# IO_connections.net
KiCad netlist of a schematic drawn in Altium Designer
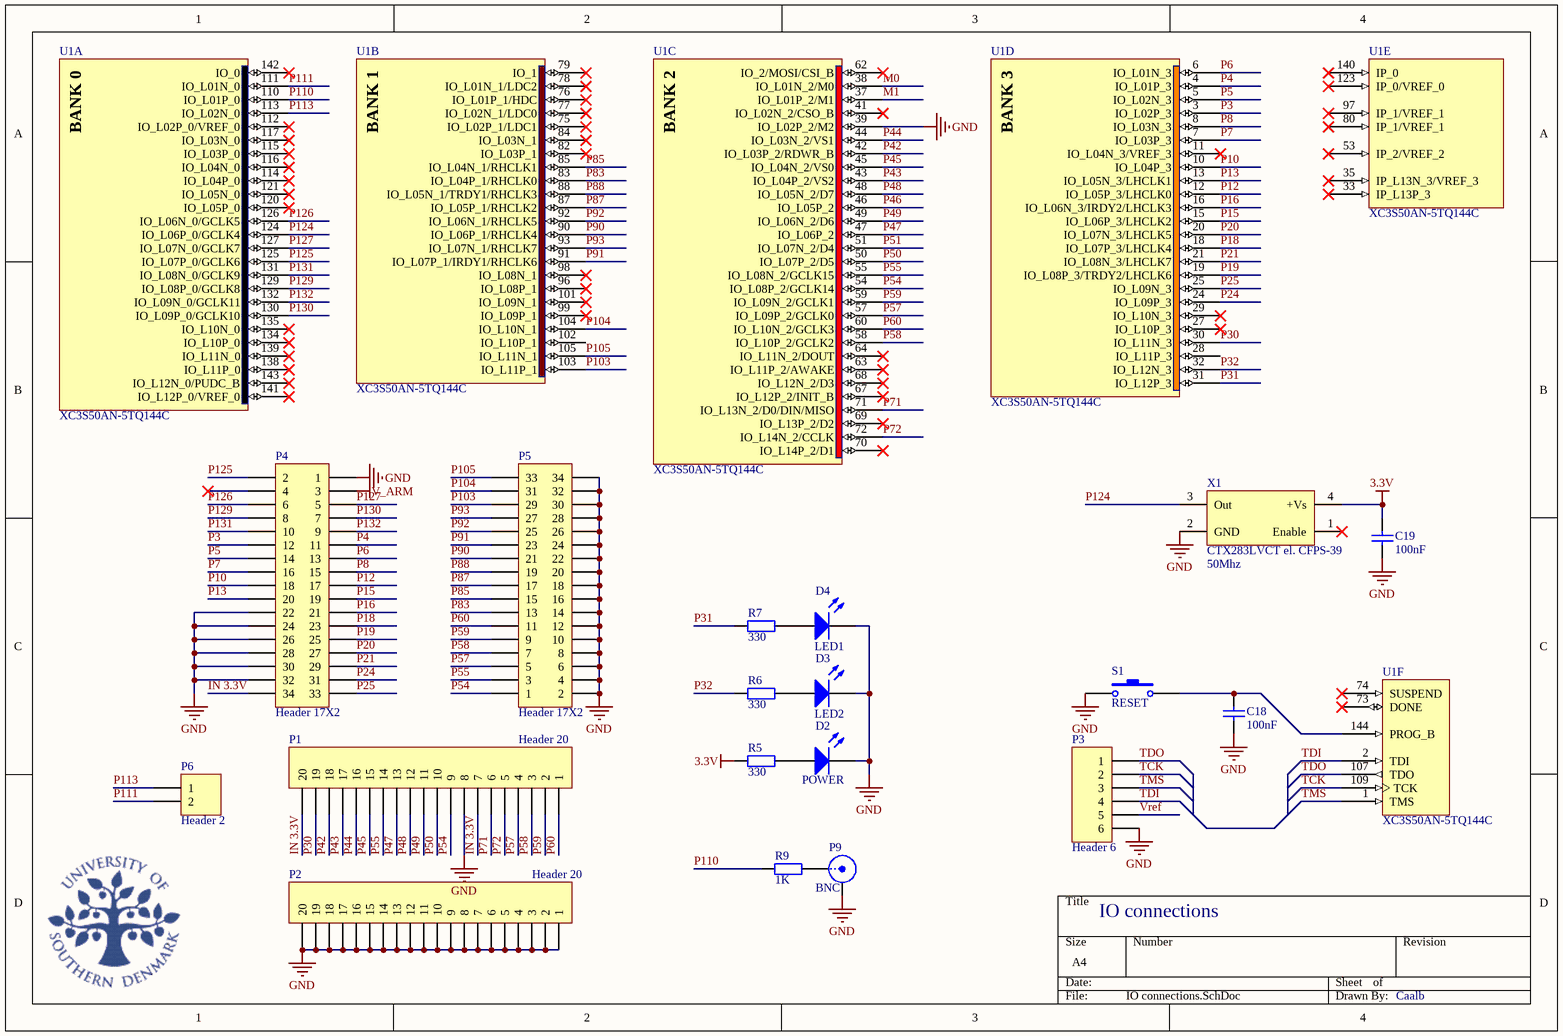
[diagram p0: IO connections.SchDoc]

(export (version "E")
  (design (tool "Eeschema 10.0.6"))
  (components
    (comp (ref "C18")
      (value "100nF")
      (footprint "0805")
      (description "!Capacitor")
      (fields (field (name "Comment") "Cap") (field (name "PUBLISHER") "Altium Limited"))
      (libsource (lib "Miscellaneous Devices") (part "Cap"))
    )
    (comp (ref "C19")
      (value "100nF")
      (footprint "0805")
      (description "!Capacitor")
      (fields (field (name "Comment") "Cap") (field (name "PUBLISHER") "Altium Limited"))
      (libsource (lib "Miscellaneous Devices") (part "Cap"))
    )
    (comp (ref "D2")
      (value "POWER")
      (footprint "LED1206")
      (description "LED")
      (fields (field (name "PUBLISHER") "Altium Limited"))
      (libsource (lib "Miscellaneous Devices") (part "LED0"))
    )
    (comp (ref "D3")
      (value "LED2")
      (footprint "LED1206")
      (description "LED")
      (fields (field (name "PUBLISHER") "Altium Limited"))
      (libsource (lib "Miscellaneous Devices") (part "LED0"))
    )
    (comp (ref "D4")
      (value "LED1")
      (footprint "LED1206")
      (description "LED")
      (fields (field (name "PUBLISHER") "Altium Limited"))
      (libsource (lib "Miscellaneous Devices") (part "LED0"))
    )
    (comp (ref "P1")
      (value "Header 20")
      (footprint "HDR1X20 Kant Special")
      (description "Header, 20-Pin")
      (fields (field (name "PUBLISHER") "Altium Limited"))
      (libsource (lib "Miscellaneous Connectors") (part "Header 20"))
    )
    (comp (ref "P2")
      (value "Header 20")
      (footprint "HDR1X20 Kant")
      (description "Header, 20-Pin")
      (fields (field (name "PUBLISHER") "Altium Limited"))
      (libsource (lib "Miscellaneous Connectors") (part "Header 20"))
    )
    (comp (ref "P3")
      (value "Header 6")
      (footprint "HDR1X6")
      (description "Header, 6-Pin")
      (fields (field (name "PUBLISHER") "Altium Limited"))
      (libsource (lib "Miscellaneous Connectors") (part "Header 6"))
    )
    (comp (ref "P4")
      (value "Header 17X2")
      (footprint "HDR2X10/17FLAD Combi")
      (description "Header, 17-Pin, Dual row")
      (fields (field (name "PUBLISHER") "Altium Limited"))
      (libsource (lib "") (part "Header 17X2_1"))
    )
    (comp (ref "P5")
      (value "Header 17X2")
      (footprint "HDR2X17FLAD Special")
      (description "Header, 17-Pin, Dual row")
      (fields (field (name "PUBLISHER") "Altium Limited"))
      (libsource (lib "Miscellaneous Connectors") (part "Header 17X2"))
    )
    (comp (ref "P6")
      (value "Header 2")
      (footprint "HDR1X2")
      (description "Header, 2-Pin")
      (fields (field (name "PUBLISHER") "Altium Limited"))
      (libsource (lib "Miscellaneous Connectors") (part "Header 2"))
    )
    (comp (ref "P9")
      (value "BNC")
      (footprint "Miniature Coaxial Connectors")
      (description "Miniature Coaxial Connectors")
      (fields (field (name "PUBLISHER") "Altium Limited"))
      (libsource (lib "Miscellaneous Connectors") (part "BNC"))
    )
    (comp (ref "R5")
      (value "330")
      (footprint "0805")
      (description "!Resistor")
      (fields (field (name "Comment") "Res2") (field (name "PUBLISHER") "Altium Limited"))
      (libsource (lib "Miscellaneous Devices") (part "Res2"))
    )
    (comp (ref "R6")
      (value "330")
      (footprint "0805")
      (description "!Resistor")
      (fields (field (name "Comment") "Res2") (field (name "PUBLISHER") "Altium Limited"))
      (libsource (lib "Miscellaneous Devices") (part "Res2"))
    )
    (comp (ref "R7")
      (value "330")
      (footprint "0805")
      (description "!Resistor")
      (fields (field (name "Comment") "Res2") (field (name "PUBLISHER") "Altium Limited"))
      (libsource (lib "Miscellaneous Devices") (part "Res2"))
    )
    (comp (ref "R9")
      (value "1K")
      (footprint "0805")
      (description "!Resistor")
      (fields (field (name "Comment") "Res2") (field (name "PUBLISHER") "Altium Limited"))
      (libsource (lib "") (part "Res2_1"))
    )
    (comp (ref "S1")
      (value "RESET")
      (footprint "B3U-3000P")
      (description "Switch")
      (fields (field (name "PUBLISHER") "Altium Limited"))
      (libsource (lib "Miscellaneous Devices") (part "SW-PB"))
    )
    (comp (ref "U1")
      (value "XC3S50AN-5TQ144C")
      (footprint "TQ144_L")
      (description "Spartan-3AN Non-Volatile FPGA, 108 User I/Os, 144-Pin TQFP, High Performance, Commercial Grade")
      (fields (field (name "PUBLISHER") "Altium Limited"))
      (libsource (lib "Xilinx Spartan-3AN") (part "XC3S50AN-5TQ144C"))
    )
    (comp (ref "X1")
      (value "CTX283LVCT el. CFPS-39")
      (footprint "CB3LV-3C/CFPS-39")
      (description "3.3V, ultra minature surface mount oscillator")
      (fields (field (name "ALTIUM_VALUE") "50Mhz"))
      (libsource (lib "DivLib") (part "CFPS-39"))
    )
  )
  (nets
    (net (code "1") (name "/IN 3.3V") (class "Default")
      (node (ref "P1") (pin "20") (pinfunction "20_20") (pintype "passive"))
      (node (ref "P1") (pin "7") (pinfunction "7_7") (pintype "passive"))
      (node (ref "P4") (pin "34") (pinfunction "34_34") (pintype "passive"))
    )
    (net (code "2") (name "/M0") (class "Default")
      (node (ref "U1") (pin "38") (pinfunction "IO_L01N_2/M0_38") (pintype "bidirectional"))
    )
    (net (code "3") (name "/M1") (class "Default")
      (node (ref "U1") (pin "37") (pinfunction "IO_L01P_2/M1_37") (pintype "bidirectional"))
    )
    (net (code "4") (name "/P3") (class "Default")
      (node (ref "P4") (pin "12") (pinfunction "12_12") (pintype "passive"))
      (node (ref "U1") (pin "3") (pinfunction "IO_L02P_3_3") (pintype "bidirectional"))
    )
    (net (code "5") (name "/P4") (class "Default")
      (node (ref "P4") (pin "11") (pinfunction "11_11") (pintype "passive"))
      (node (ref "U1") (pin "4") (pinfunction "IO_L01P_3_4") (pintype "bidirectional"))
    )
    (net (code "6") (name "/P5") (class "Default")
      (node (ref "P4") (pin "14") (pinfunction "14_14") (pintype "passive"))
      (node (ref "U1") (pin "5") (pinfunction "IO_L02N_3_5") (pintype "bidirectional"))
    )
    (net (code "7") (name "/P6") (class "Default")
      (node (ref "P4") (pin "13") (pinfunction "13_13") (pintype "passive"))
      (node (ref "U1") (pin "6") (pinfunction "IO_L01N_3_6") (pintype "bidirectional"))
    )
    (net (code "8") (name "/P7") (class "Default")
      (node (ref "P4") (pin "16") (pinfunction "16_16") (pintype "passive"))
      (node (ref "U1") (pin "7") (pinfunction "IO_L03P_3_7") (pintype "bidirectional"))
    )
    (net (code "9") (name "/P8") (class "Default")
      (node (ref "P4") (pin "15") (pinfunction "15_15") (pintype "passive"))
      (node (ref "U1") (pin "8") (pinfunction "IO_L03N_3_8") (pintype "bidirectional"))
    )
    (net (code "10") (name "/P10") (class "Default")
      (node (ref "P4") (pin "18") (pinfunction "18_18") (pintype "passive"))
      (node (ref "U1") (pin "10") (pinfunction "IO_L04P_3_10") (pintype "bidirectional"))
    )
    (net (code "11") (name "/P12") (class "Default")
      (node (ref "P4") (pin "17") (pinfunction "17_17") (pintype "passive"))
      (node (ref "U1") (pin "12") (pinfunction "IO_L05P_3/LHCLK0_12") (pintype "bidirectional"))
    )
    (net (code "12") (name "/P13") (class "Default")
      (node (ref "P4") (pin "20") (pinfunction "20_20") (pintype "passive"))
      (node (ref "U1") (pin "13") (pinfunction "IO_L05N_3/LHCLK1_13") (pintype "bidirectional"))
    )
    (net (code "13") (name "/P15") (class "Default")
      (node (ref "P4") (pin "19") (pinfunction "19_19") (pintype "passive"))
      (node (ref "U1") (pin "15") (pinfunction "IO_L06P_3/LHCLK2_15") (pintype "bidirectional"))
    )
    (net (code "14") (name "/P16") (class "Default")
      (node (ref "P4") (pin "21") (pinfunction "21_21") (pintype "passive"))
      (node (ref "U1") (pin "16") (pinfunction "IO_L06N_3/IRDY2/LHCLK3_16") (pintype "bidirectional"))
    )
    (net (code "15") (name "/P18") (class "Default")
      (node (ref "P4") (pin "23") (pinfunction "23_23") (pintype "passive"))
      (node (ref "U1") (pin "18") (pinfunction "IO_L07P_3/LHCLK4_18") (pintype "bidirectional"))
    )
    (net (code "16") (name "/P19") (class "Default")
      (node (ref "P4") (pin "25") (pinfunction "25_25") (pintype "passive"))
      (node (ref "U1") (pin "19") (pinfunction "IO_L08P_3/TRDY2/LHCLK6_19") (pintype "bidirectional"))
    )
    (net (code "17") (name "/P20") (class "Default")
      (node (ref "P4") (pin "27") (pinfunction "27_27") (pintype "passive"))
      (node (ref "U1") (pin "20") (pinfunction "IO_L07N_3/LHCLK5_20") (pintype "bidirectional"))
    )
    (net (code "18") (name "/P21") (class "Default")
      (node (ref "P4") (pin "29") (pinfunction "29_29") (pintype "passive"))
      (node (ref "U1") (pin "21") (pinfunction "IO_L08N_3/LHCLK7_21") (pintype "bidirectional"))
    )
    (net (code "19") (name "/P24") (class "Default")
      (node (ref "P4") (pin "31") (pinfunction "31_31") (pintype "passive"))
      (node (ref "U1") (pin "24") (pinfunction "IO_L09P_3_24") (pintype "bidirectional"))
    )
    (net (code "20") (name "/P25") (class "Default")
      (node (ref "P4") (pin "33") (pinfunction "33_33") (pintype "passive"))
      (node (ref "U1") (pin "25") (pinfunction "IO_L09N_3_25") (pintype "bidirectional"))
    )
    (net (code "21") (name "/P30") (class "Default")
      (node (ref "P1") (pin "19") (pinfunction "19_19") (pintype "passive"))
      (node (ref "U1") (pin "30") (pinfunction "IO_L11N_3_30") (pintype "bidirectional"))
    )
    (net (code "22") (name "/P31") (class "Default")
      (node (ref "R7") (pin "2") (pinfunction "2_2") (pintype "passive"))
      (node (ref "U1") (pin "31") (pinfunction "IO_L12P_3_31") (pintype "bidirectional"))
    )
    (net (code "23") (name "/P32") (class "Default")
      (node (ref "R6") (pin "2") (pinfunction "2_2") (pintype "passive"))
      (node (ref "U1") (pin "32") (pinfunction "IO_L12N_3_32") (pintype "bidirectional"))
    )
    (net (code "24") (name "/P42") (class "Default")
      (node (ref "P1") (pin "18") (pinfunction "18_18") (pintype "passive"))
      (node (ref "U1") (pin "42") (pinfunction "IO_L03P_2/RDWR_B_42") (pintype "bidirectional"))
    )
    (net (code "25") (name "/P43") (class "Default")
      (node (ref "P1") (pin "17") (pinfunction "17_17") (pintype "passive"))
      (node (ref "U1") (pin "43") (pinfunction "IO_L04P_2/VS2_43") (pintype "bidirectional"))
    )
    (net (code "26") (name "/P44") (class "Default")
      (node (ref "P1") (pin "16") (pinfunction "16_16") (pintype "passive"))
      (node (ref "U1") (pin "44") (pinfunction "IO_L03N_2/VS1_44") (pintype "bidirectional"))
    )
    (net (code "27") (name "/P45") (class "Default")
      (node (ref "P1") (pin "15") (pinfunction "15_15") (pintype "passive"))
      (node (ref "U1") (pin "45") (pinfunction "IO_L04N_2/VS0_45") (pintype "bidirectional"))
    )
    (net (code "28") (name "/P46") (class "Default")
      (node (ref "U1") (pin "46") (pinfunction "IO_L05P_2_46") (pintype "bidirectional"))
    )
    (net (code "29") (name "/P47") (class "Default")
      (node (ref "P1") (pin "13") (pinfunction "13_13") (pintype "passive"))
      (node (ref "U1") (pin "47") (pinfunction "IO_L06P_2_47") (pintype "bidirectional"))
    )
    (net (code "30") (name "/P48") (class "Default")
      (node (ref "P1") (pin "12") (pinfunction "12_12") (pintype "passive"))
      (node (ref "U1") (pin "48") (pinfunction "IO_L05N_2/D7_48") (pintype "bidirectional"))
    )
    (net (code "31") (name "/P49") (class "Default")
      (node (ref "P1") (pin "11") (pinfunction "11_11") (pintype "passive"))
      (node (ref "U1") (pin "49") (pinfunction "IO_L06N_2/D6_49") (pintype "bidirectional"))
    )
    (net (code "32") (name "/P50") (class "Default")
      (node (ref "P1") (pin "10") (pinfunction "10_10") (pintype "passive"))
      (node (ref "U1") (pin "50") (pinfunction "IO_L07P_2/D5_50") (pintype "bidirectional"))
    )
    (net (code "33") (name "/P51") (class "Default")
      (node (ref "U1") (pin "51") (pinfunction "IO_L07N_2/D4_51") (pintype "bidirectional"))
    )
    (net (code "34") (name "/P54") (class "Default")
      (node (ref "P1") (pin "9") (pinfunction "9_9") (pintype "passive"))
      (node (ref "P5") (pin "1") (pinfunction "1_1") (pintype "passive"))
      (node (ref "U1") (pin "54") (pinfunction "IO_L08P_2/GCLK14_54") (pintype "bidirectional"))
    )
    (net (code "35") (name "/P55") (class "Default")
      (node (ref "P1") (pin "14") (pinfunction "14_14") (pintype "passive"))
      (node (ref "P5") (pin "3") (pinfunction "3_3") (pintype "passive"))
      (node (ref "U1") (pin "55") (pinfunction "IO_L08N_2/GCLK15_55") (pintype "bidirectional"))
    )
    (net (code "36") (name "/P57") (class "Default")
      (node (ref "P1") (pin "4") (pinfunction "4_4") (pintype "passive"))
      (node (ref "P5") (pin "5") (pinfunction "5_5") (pintype "passive"))
      (node (ref "U1") (pin "57") (pinfunction "IO_L09P_2/GCLK0_57") (pintype "bidirectional"))
    )
    (net (code "37") (name "/P58") (class "Default")
      (node (ref "P1") (pin "3") (pinfunction "3_3") (pintype "passive"))
      (node (ref "P5") (pin "7") (pinfunction "7_7") (pintype "passive"))
      (node (ref "U1") (pin "58") (pinfunction "IO_L10P_2/GCLK2_58") (pintype "bidirectional"))
    )
    (net (code "38") (name "/P59") (class "Default")
      (node (ref "P1") (pin "2") (pinfunction "2_2") (pintype "passive"))
      (node (ref "P5") (pin "9") (pinfunction "9_9") (pintype "passive"))
      (node (ref "U1") (pin "59") (pinfunction "IO_L09N_2/GCLK1_59") (pintype "bidirectional"))
    )
    (net (code "39") (name "/P60") (class "Default")
      (node (ref "P1") (pin "1") (pinfunction "1_1") (pintype "passive"))
      (node (ref "P5") (pin "11") (pinfunction "11_11") (pintype "passive"))
      (node (ref "U1") (pin "60") (pinfunction "IO_L10N_2/GCLK3_60") (pintype "bidirectional"))
    )
    (net (code "40") (name "/P71") (class "Default")
      (node (ref "P1") (pin "6") (pinfunction "6_6") (pintype "passive"))
      (node (ref "U1") (pin "71") (pinfunction "IO_L13N_2/D0/DIN/MISO_71") (pintype "bidirectional"))
    )
    (net (code "41") (name "/P72") (class "Default")
      (node (ref "P1") (pin "5") (pinfunction "5_5") (pintype "passive"))
      (node (ref "U1") (pin "72") (pinfunction "IO_L14N_2/CCLK_72") (pintype "bidirectional"))
    )
    (net (code "42") (name "/P83") (class "Default")
      (node (ref "P5") (pin "13") (pinfunction "13_13") (pintype "passive"))
      (node (ref "U1") (pin "83") (pinfunction "IO_L04P_1/RHCLK0_83") (pintype "bidirectional"))
    )
    (net (code "43") (name "/P85") (class "Default")
      (node (ref "P5") (pin "15") (pinfunction "15_15") (pintype "passive"))
      (node (ref "U1") (pin "85") (pinfunction "IO_L04N_1/RHCLK1_85") (pintype "bidirectional"))
    )
    (net (code "44") (name "/P87") (class "Default")
      (node (ref "P5") (pin "17") (pinfunction "17_17") (pintype "passive"))
      (node (ref "U1") (pin "87") (pinfunction "IO_L05P_1/RHCLK2_87") (pintype "bidirectional"))
    )
    (net (code "45") (name "/P88") (class "Default")
      (node (ref "P5") (pin "19") (pinfunction "19_19") (pintype "passive"))
      (node (ref "U1") (pin "88") (pinfunction "IO_L05N_1/TRDY1/RHCLK3_88") (pintype "bidirectional"))
    )
    (net (code "46") (name "/P90") (class "Default")
      (node (ref "P5") (pin "21") (pinfunction "21_21") (pintype "passive"))
      (node (ref "U1") (pin "90") (pinfunction "IO_L06P_1/RHCLK4_90") (pintype "bidirectional"))
    )
    (net (code "47") (name "/P91") (class "Default")
      (node (ref "P5") (pin "23") (pinfunction "23_23") (pintype "passive"))
      (node (ref "U1") (pin "91") (pinfunction "IO_L07P_1/IRDY1/RHCLK6_91") (pintype "bidirectional"))
    )
    (net (code "48") (name "/P92") (class "Default")
      (node (ref "P5") (pin "25") (pinfunction "25_25") (pintype "passive"))
      (node (ref "U1") (pin "92") (pinfunction "IO_L06N_1/RHCLK5_92") (pintype "bidirectional"))
    )
    (net (code "49") (name "/P93") (class "Default")
      (node (ref "P5") (pin "27") (pinfunction "27_27") (pintype "passive"))
      (node (ref "U1") (pin "93") (pinfunction "IO_L07N_1/RHCLK7_93") (pintype "bidirectional"))
    )
    (net (code "50") (name "/P103") (class "Default")
      (node (ref "P5") (pin "29") (pinfunction "29_29") (pintype "passive"))
      (node (ref "U1") (pin "103") (pinfunction "IO_L11P_1_103") (pintype "bidirectional"))
    )
    (net (code "51") (name "/P104") (class "Default")
      (node (ref "P5") (pin "31") (pinfunction "31_31") (pintype "passive"))
      (node (ref "U1") (pin "104") (pinfunction "IO_L10N_1_104") (pintype "bidirectional"))
    )
    (net (code "52") (name "/P105") (class "Default")
      (node (ref "P5") (pin "33") (pinfunction "33_33") (pintype "passive"))
      (node (ref "U1") (pin "105") (pinfunction "IO_L11N_1_105") (pintype "bidirectional"))
    )
    (net (code "53") (name "/P110") (class "Default")
      (node (ref "R9") (pin "1") (pinfunction "1_1") (pintype "passive"))
      (node (ref "U1") (pin "110") (pinfunction "IO_L01P_0_110") (pintype "bidirectional"))
    )
    (net (code "54") (name "/P111") (class "Default")
      (node (ref "P6") (pin "2") (pinfunction "2_2") (pintype "passive"))
      (node (ref "U1") (pin "111") (pinfunction "IO_L01N_0_111") (pintype "bidirectional"))
    )
    (net (code "55") (name "/P113") (class "Default")
      (node (ref "P6") (pin "1") (pinfunction "1_1") (pintype "passive"))
      (node (ref "U1") (pin "113") (pinfunction "IO_L02N_0_113") (pintype "bidirectional"))
    )
    (net (code "56") (name "/P124") (class "Default")
      (node (ref "U1") (pin "124") (pinfunction "IO_L06P_0/GCLK4_124") (pintype "bidirectional"))
      (node (ref "X1") (pin "3") (pinfunction "Out_3") (pintype "power_in"))
    )
    (net (code "57") (name "/P125") (class "Default")
      (node (ref "P4") (pin "2") (pinfunction "2_2") (pintype "passive"))
      (node (ref "U1") (pin "125") (pinfunction "IO_L07P_0/GCLK6_125") (pintype "bidirectional"))
    )
    (net (code "58") (name "/P126") (class "Default")
      (node (ref "P4") (pin "6") (pinfunction "6_6") (pintype "passive"))
      (node (ref "U1") (pin "126") (pinfunction "IO_L06N_0/GCLK5_126") (pintype "bidirectional"))
    )
    (net (code "59") (name "/P127") (class "Default")
      (node (ref "P4") (pin "5") (pinfunction "5_5") (pintype "passive"))
      (node (ref "U1") (pin "127") (pinfunction "IO_L07N_0/GCLK7_127") (pintype "bidirectional"))
    )
    (net (code "60") (name "/P129") (class "Default")
      (node (ref "P4") (pin "8") (pinfunction "8_8") (pintype "passive"))
      (node (ref "U1") (pin "129") (pinfunction "IO_L08P_0/GCLK8_129") (pintype "bidirectional"))
    )
    (net (code "61") (name "/P130") (class "Default")
      (node (ref "P4") (pin "7") (pinfunction "7_7") (pintype "passive"))
      (node (ref "U1") (pin "130") (pinfunction "IO_L09P_0/GCLK10_130") (pintype "bidirectional"))
    )
    (net (code "62") (name "/P131") (class "Default")
      (node (ref "P4") (pin "10") (pinfunction "10_10") (pintype "passive"))
      (node (ref "U1") (pin "131") (pinfunction "IO_L08N_0/GCLK9_131") (pintype "bidirectional"))
    )
    (net (code "63") (name "/P132") (class "Default")
      (node (ref "P4") (pin "9") (pinfunction "9_9") (pintype "passive"))
      (node (ref "U1") (pin "132") (pinfunction "IO_L09N_0/GCLK11_132") (pintype "bidirectional"))
    )
    (net (code "64") (name "/TCK") (class "Default")
      (node (ref "P3") (pin "2") (pinfunction "2_2") (pintype "passive"))
      (node (ref "U1") (pin "109") (pinfunction "TCK_109") (pintype "input"))
    )
    (net (code "65") (name "/TDI") (class "Default")
      (node (ref "P3") (pin "4") (pinfunction "4_4") (pintype "passive"))
      (node (ref "U1") (pin "2") (pinfunction "TDI_2") (pintype "input"))
    )
    (net (code "66") (name "/TDO") (class "Default")
      (node (ref "P3") (pin "1") (pinfunction "1_1") (pintype "passive"))
      (node (ref "U1") (pin "107") (pinfunction "TDO_107") (pintype "output"))
    )
    (net (code "67") (name "/TMS") (class "Default")
      (node (ref "P3") (pin "3") (pinfunction "3_3") (pintype "passive"))
      (node (ref "U1") (pin "1") (pinfunction "TMS_1") (pintype "input"))
    )
    (net (code "68") (name "/Vref") (class "Default")
      (node (ref "P3") (pin "5") (pinfunction "5_5") (pintype "passive"))
    )
    (net (code "69") (name "3.3V") (class "Default")
      (node (ref "C19") (pin "2") (pinfunction "2_2") (pintype "passive"))
      (node (ref "R5") (pin "2") (pinfunction "2_2") (pintype "passive"))
      (node (ref "X1") (pin "4") (pinfunction "+Vs_4") (pintype "power_in"))
    )
    (net (code "70") (name "GND") (class "Default")
      (node (ref "C18") (pin "1") (pinfunction "1_1") (pintype "passive"))
      (node (ref "C19") (pin "1") (pinfunction "1_1") (pintype "passive"))
      (node (ref "D2") (pin "2") (pinfunction "K_2") (pintype "passive"))
      (node (ref "D3") (pin "2") (pinfunction "K_2") (pintype "passive"))
      (node (ref "D4") (pin "2") (pinfunction "K_2") (pintype "passive"))
      (node (ref "P1") (pin "8") (pinfunction "8_8") (pintype "passive"))
      (node (ref "P2") (pin "1") (pinfunction "1_1") (pintype "passive"))
      (node (ref "P2") (pin "10") (pinfunction "10_10") (pintype "passive"))
      (node (ref "P2") (pin "11") (pinfunction "11_11") (pintype "passive"))
      (node (ref "P2") (pin "12") (pinfunction "12_12") (pintype "passive"))
      (node (ref "P2") (pin "13") (pinfunction "13_13") (pintype "passive"))
      (node (ref "P2") (pin "14") (pinfunction "14_14") (pintype "passive"))
      (node (ref "P2") (pin "15") (pinfunction "15_15") (pintype "passive"))
      (node (ref "P2") (pin "16") (pinfunction "16_16") (pintype "passive"))
      (node (ref "P2") (pin "17") (pinfunction "17_17") (pintype "passive"))
      (node (ref "P2") (pin "18") (pinfunction "18_18") (pintype "passive"))
      (node (ref "P2") (pin "19") (pinfunction "19_19") (pintype "passive"))
      (node (ref "P2") (pin "2") (pinfunction "2_2") (pintype "passive"))
      (node (ref "P2") (pin "20") (pinfunction "20_20") (pintype "passive"))
      (node (ref "P2") (pin "3") (pinfunction "3_3") (pintype "passive"))
      (node (ref "P2") (pin "4") (pinfunction "4_4") (pintype "passive"))
      (node (ref "P2") (pin "5") (pinfunction "5_5") (pintype "passive"))
      (node (ref "P2") (pin "6") (pinfunction "6_6") (pintype "passive"))
      (node (ref "P2") (pin "7") (pinfunction "7_7") (pintype "passive"))
      (node (ref "P2") (pin "8") (pinfunction "8_8") (pintype "passive"))
      (node (ref "P2") (pin "9") (pinfunction "9_9") (pintype "passive"))
      (node (ref "P3") (pin "6") (pinfunction "6_6") (pintype "passive"))
      (node (ref "P4") (pin "1") (pinfunction "1_1") (pintype "passive"))
      (node (ref "P4") (pin "22") (pinfunction "22_22") (pintype "passive"))
      (node (ref "P4") (pin "24") (pinfunction "24_24") (pintype "passive"))
      (node (ref "P4") (pin "26") (pinfunction "26_26") (pintype "passive"))
      (node (ref "P4") (pin "28") (pinfunction "28_28") (pintype "passive"))
      (node (ref "P4") (pin "30") (pinfunction "30_30") (pintype "passive"))
      (node (ref "P4") (pin "32") (pinfunction "32_32") (pintype "passive"))
      (node (ref "P5") (pin "10") (pinfunction "10_10") (pintype "passive"))
      (node (ref "P5") (pin "12") (pinfunction "12_12") (pintype "passive"))
      (node (ref "P5") (pin "14") (pinfunction "14_14") (pintype "passive"))
      (node (ref "P5") (pin "16") (pinfunction "16_16") (pintype "passive"))
      (node (ref "P5") (pin "18") (pinfunction "18_18") (pintype "passive"))
      (node (ref "P5") (pin "2") (pinfunction "2_2") (pintype "passive"))
      (node (ref "P5") (pin "20") (pinfunction "20_20") (pintype "passive"))
      (node (ref "P5") (pin "22") (pinfunction "22_22") (pintype "passive"))
      (node (ref "P5") (pin "24") (pinfunction "24_24") (pintype "passive"))
      (node (ref "P5") (pin "26") (pinfunction "26_26") (pintype "passive"))
      (node (ref "P5") (pin "28") (pinfunction "28_28") (pintype "passive"))
      (node (ref "P5") (pin "30") (pinfunction "30_30") (pintype "passive"))
      (node (ref "P5") (pin "32") (pinfunction "32_32") (pintype "passive"))
      (node (ref "P5") (pin "34") (pinfunction "34_34") (pintype "passive"))
      (node (ref "P5") (pin "4") (pinfunction "4_4") (pintype "passive"))
      (node (ref "P5") (pin "6") (pinfunction "6_6") (pintype "passive"))
      (node (ref "P5") (pin "8") (pinfunction "8_8") (pintype "passive"))
      (node (ref "P9") (pin "2") (pinfunction "Y_2") (pintype "passive"))
      (node (ref "S1") (pin "1") (pinfunction "1_1") (pintype "passive"))
      (node (ref "U1") (pin "39") (pinfunction "IO_L02P_2/M2_39") (pintype "bidirectional"))
      (node (ref "X1") (pin "2") (pinfunction "GND_2") (pintype "power_in"))
    )
    (net (code "71") (name "Net-(D2-A)") (class "Default")
      (node (ref "D2") (pin "1") (pinfunction "A_1") (pintype "passive"))
      (node (ref "R5") (pin "1") (pinfunction "1_1") (pintype "passive"))
    )
    (net (code "72") (name "Net-(D3-A)") (class "Default")
      (node (ref "D3") (pin "1") (pinfunction "A_1") (pintype "passive"))
      (node (ref "R6") (pin "1") (pinfunction "1_1") (pintype "passive"))
    )
    (net (code "73") (name "Net-(D4-A)") (class "Default")
      (node (ref "D4") (pin "1") (pinfunction "A_1") (pintype "passive"))
      (node (ref "R7") (pin "1") (pinfunction "1_1") (pintype "passive"))
    )
    (net (code "74") (name "Net-(P9-X)") (class "Default")
      (node (ref "P9") (pin "1") (pinfunction "X_1") (pintype "passive"))
      (node (ref "R9") (pin "2") (pinfunction "2_2") (pintype "passive"))
    )
    (net (code "75") (name "Net-(U1F-PROG_B)") (class "Default")
      (node (ref "C18") (pin "2") (pinfunction "2_2") (pintype "passive"))
      (node (ref "S1") (pin "2") (pinfunction "2_2") (pintype "passive"))
      (node (ref "U1") (pin "144") (pinfunction "PROG_B_144") (pintype "input"))
    )
    (net (code "76") (name "V_ARM") (class "Default")
      (node (ref "P4") (pin "3") (pinfunction "3_3") (pintype "passive"))
    )
    (net (code "77") (name "unconnected-(P4-Pad4)") (class "Default")
      (node (ref "P4") (pin "4") (pinfunction "4_4") (pintype "passive+no_connect"))
    )
    (net (code "78") (name "unconnected-(U1A-IO_0-Pad142)") (class "Default")
      (node (ref "U1") (pin "142") (pinfunction "IO_0_142") (pintype "bidirectional+no_connect"))
    )
    (net (code "79") (name "unconnected-(U1A-IO_L02P_0{slash}VREF_0-Pad112)") (class "Default")
      (node (ref "U1") (pin "112") (pinfunction "IO_L02P_0/VREF_0_112") (pintype "bidirectional+no_connect"))
    )
    (net (code "80") (name "unconnected-(U1A-IO_L03N_0-Pad117)") (class "Default")
      (node (ref "U1") (pin "117") (pinfunction "IO_L03N_0_117") (pintype "bidirectional+no_connect"))
    )
    (net (code "81") (name "unconnected-(U1A-IO_L03P_0-Pad115)") (class "Default")
      (node (ref "U1") (pin "115") (pinfunction "IO_L03P_0_115") (pintype "bidirectional+no_connect"))
    )
    (net (code "82") (name "unconnected-(U1A-IO_L04N_0-Pad116)") (class "Default")
      (node (ref "U1") (pin "116") (pinfunction "IO_L04N_0_116") (pintype "bidirectional+no_connect"))
    )
    (net (code "83") (name "unconnected-(U1A-IO_L04P_0-Pad114)") (class "Default")
      (node (ref "U1") (pin "114") (pinfunction "IO_L04P_0_114") (pintype "bidirectional+no_connect"))
    )
    (net (code "84") (name "unconnected-(U1A-IO_L05N_0-Pad121)") (class "Default")
      (node (ref "U1") (pin "121") (pinfunction "IO_L05N_0_121") (pintype "bidirectional+no_connect"))
    )
    (net (code "85") (name "unconnected-(U1A-IO_L05P_0-Pad120)") (class "Default")
      (node (ref "U1") (pin "120") (pinfunction "IO_L05P_0_120") (pintype "bidirectional+no_connect"))
    )
    (net (code "86") (name "unconnected-(U1A-IO_L10N_0-Pad135)") (class "Default")
      (node (ref "U1") (pin "135") (pinfunction "IO_L10N_0_135") (pintype "bidirectional+no_connect"))
    )
    (net (code "87") (name "unconnected-(U1A-IO_L10P_0-Pad134)") (class "Default")
      (node (ref "U1") (pin "134") (pinfunction "IO_L10P_0_134") (pintype "bidirectional+no_connect"))
    )
    (net (code "88") (name "unconnected-(U1A-IO_L11N_0-Pad139)") (class "Default")
      (node (ref "U1") (pin "139") (pinfunction "IO_L11N_0_139") (pintype "bidirectional+no_connect"))
    )
    (net (code "89") (name "unconnected-(U1A-IO_L11P_0-Pad138)") (class "Default")
      (node (ref "U1") (pin "138") (pinfunction "IO_L11P_0_138") (pintype "bidirectional+no_connect"))
    )
    (net (code "90") (name "unconnected-(U1A-IO_L12N_0{slash}PUDC_B-Pad143)") (class "Default")
      (node (ref "U1") (pin "143") (pinfunction "IO_L12N_0/PUDC_B_143") (pintype "bidirectional+no_connect"))
    )
    (net (code "91") (name "unconnected-(U1A-IO_L12P_0{slash}VREF_0-Pad141)") (class "Default")
      (node (ref "U1") (pin "141") (pinfunction "IO_L12P_0/VREF_0_141") (pintype "bidirectional+no_connect"))
    )
    (net (code "92") (name "unconnected-(U1B-IO_1-Pad79)") (class "Default")
      (node (ref "U1") (pin "79") (pinfunction "IO_1_79") (pintype "bidirectional+no_connect"))
    )
    (net (code "93") (name "unconnected-(U1B-IO_L01N_1{slash}LDC2-Pad78)") (class "Default")
      (node (ref "U1") (pin "78") (pinfunction "IO_L01N_1/LDC2_78") (pintype "bidirectional+no_connect"))
    )
    (net (code "94") (name "unconnected-(U1B-IO_L01P_1{slash}HDC-Pad76)") (class "Default")
      (node (ref "U1") (pin "76") (pinfunction "IO_L01P_1/HDC_76") (pintype "bidirectional+no_connect"))
    )
    (net (code "95") (name "unconnected-(U1B-IO_L02N_1{slash}LDC0-Pad77)") (class "Default")
      (node (ref "U1") (pin "77") (pinfunction "IO_L02N_1/LDC0_77") (pintype "bidirectional+no_connect"))
    )
    (net (code "96") (name "unconnected-(U1B-IO_L02P_1{slash}LDC1-Pad75)") (class "Default")
      (node (ref "U1") (pin "75") (pinfunction "IO_L02P_1/LDC1_75") (pintype "bidirectional+no_connect"))
    )
    (net (code "97") (name "unconnected-(U1B-IO_L03N_1-Pad84)") (class "Default")
      (node (ref "U1") (pin "84") (pinfunction "IO_L03N_1_84") (pintype "bidirectional+no_connect"))
    )
    (net (code "98") (name "unconnected-(U1B-IO_L03P_1-Pad82)") (class "Default")
      (node (ref "U1") (pin "82") (pinfunction "IO_L03P_1_82") (pintype "bidirectional+no_connect"))
    )
    (net (code "99") (name "unconnected-(U1B-IO_L08N_1-Pad98)") (class "Default")
      (node (ref "U1") (pin "98") (pinfunction "IO_L08N_1_98") (pintype "bidirectional+no_connect"))
    )
    (net (code "100") (name "unconnected-(U1B-IO_L08P_1-Pad96)") (class "Default")
      (node (ref "U1") (pin "96") (pinfunction "IO_L08P_1_96") (pintype "bidirectional+no_connect"))
    )
    (net (code "101") (name "unconnected-(U1B-IO_L09N_1-Pad101)") (class "Default")
      (node (ref "U1") (pin "101") (pinfunction "IO_L09N_1_101") (pintype "bidirectional+no_connect"))
    )
    (net (code "102") (name "unconnected-(U1B-IO_L09P_1-Pad99)") (class "Default")
      (node (ref "U1") (pin "99") (pinfunction "IO_L09P_1_99") (pintype "bidirectional+no_connect"))
    )
    (net (code "103") (name "unconnected-(U1B-IO_L10P_1-Pad102)") (class "Default")
      (node (ref "U1") (pin "102") (pinfunction "IO_L10P_1_102") (pintype "bidirectional"))
    )
    (net (code "104") (name "unconnected-(U1C-IO_2{slash}MOSI{slash}CSI_B-Pad62)") (class "Default")
      (node (ref "U1") (pin "62") (pinfunction "IO_2/MOSI/CSI_B_62") (pintype "bidirectional+no_connect"))
    )
    (net (code "105") (name "unconnected-(U1C-IO_L02N_2{slash}CSO_B-Pad41)") (class "Default")
      (node (ref "U1") (pin "41") (pinfunction "IO_L02N_2/CSO_B_41") (pintype "bidirectional+no_connect"))
    )
    (net (code "106") (name "unconnected-(U1C-IO_L11N_2{slash}DOUT-Pad64)") (class "Default")
      (node (ref "U1") (pin "64") (pinfunction "IO_L11N_2/DOUT_64") (pintype "bidirectional+no_connect"))
    )
    (net (code "107") (name "unconnected-(U1C-IO_L11P_2{slash}AWAKE-Pad63)") (class "Default")
      (node (ref "U1") (pin "63") (pinfunction "IO_L11P_2/AWAKE_63") (pintype "bidirectional+no_connect"))
    )
    (net (code "108") (name "unconnected-(U1C-IO_L12N_2{slash}D3-Pad68)") (class "Default")
      (node (ref "U1") (pin "68") (pinfunction "IO_L12N_2/D3_68") (pintype "bidirectional+no_connect"))
    )
    (net (code "109") (name "unconnected-(U1C-IO_L12P_2{slash}INIT_B-Pad67)") (class "Default")
      (node (ref "U1") (pin "67") (pinfunction "IO_L12P_2/INIT_B_67") (pintype "bidirectional+no_connect"))
    )
    (net (code "110") (name "unconnected-(U1C-IO_L13P_2{slash}D2-Pad69)") (class "Default")
      (node (ref "U1") (pin "69") (pinfunction "IO_L13P_2/D2_69") (pintype "bidirectional+no_connect"))
    )
    (net (code "111") (name "unconnected-(U1C-IO_L14P_2{slash}D1-Pad70)") (class "Default")
      (node (ref "U1") (pin "70") (pinfunction "IO_L14P_2/D1_70") (pintype "bidirectional+no_connect"))
    )
    (net (code "112") (name "unconnected-(U1D-IO_L04N_3{slash}VREF_3-Pad11)") (class "Default")
      (node (ref "U1") (pin "11") (pinfunction "IO_L04N_3/VREF_3_11") (pintype "bidirectional+no_connect"))
    )
    (net (code "113") (name "unconnected-(U1D-IO_L10N_3-Pad29)") (class "Default")
      (node (ref "U1") (pin "29") (pinfunction "IO_L10N_3_29") (pintype "bidirectional+no_connect"))
    )
    (net (code "114") (name "unconnected-(U1D-IO_L10P_3-Pad27)") (class "Default")
      (node (ref "U1") (pin "27") (pinfunction "IO_L10P_3_27") (pintype "bidirectional+no_connect"))
    )
    (net (code "115") (name "unconnected-(U1D-IO_L11P_3-Pad28)") (class "Default")
      (node (ref "U1") (pin "28") (pinfunction "IO_L11P_3_28") (pintype "bidirectional"))
    )
    (net (code "116") (name "unconnected-(U1E-IP_0-Pad140)") (class "Default")
      (node (ref "U1") (pin "140") (pinfunction "IP_0_140") (pintype "input+no_connect"))
    )
    (net (code "117") (name "unconnected-(U1E-IP_0{slash}VREF_0-Pad123)") (class "Default")
      (node (ref "U1") (pin "123") (pinfunction "IP_0/VREF_0_123") (pintype "input+no_connect"))
    )
    (net (code "118") (name "unconnected-(U1E-IP_1{slash}VREF_1-Pad80)") (class "Default")
      (node (ref "U1") (pin "80") (pinfunction "IP_1/VREF_1_80") (pintype "input+no_connect"))
    )
    (net (code "119") (name "unconnected-(U1E-IP_1{slash}VREF_1-Pad97)") (class "Default")
      (node (ref "U1") (pin "97") (pinfunction "IP_1/VREF_1_97") (pintype "input+no_connect"))
    )
    (net (code "120") (name "unconnected-(U1E-IP_2{slash}VREF_2-Pad53)") (class "Default")
      (node (ref "U1") (pin "53") (pinfunction "IP_2/VREF_2_53") (pintype "input+no_connect"))
    )
    (net (code "121") (name "unconnected-(U1E-IP_L13N_3{slash}VREF_3-Pad35)") (class "Default")
      (node (ref "U1") (pin "35") (pinfunction "IP_L13N_3/VREF_3_35") (pintype "input+no_connect"))
    )
    (net (code "122") (name "unconnected-(U1E-IP_L13P_3-Pad33)") (class "Default")
      (node (ref "U1") (pin "33") (pinfunction "IP_L13P_3_33") (pintype "input+no_connect"))
    )
    (net (code "123") (name "unconnected-(U1F-DONE-Pad73)") (class "Default")
      (node (ref "U1") (pin "73") (pinfunction "DONE_73") (pintype "bidirectional+no_connect"))
    )
    (net (code "124") (name "unconnected-(U1F-SUSPEND-Pad74)") (class "Default")
      (node (ref "U1") (pin "74") (pinfunction "SUSPEND_74") (pintype "input+no_connect"))
    )
    (net (code "125") (name "unconnected-(X1-Enable-Pad1)") (class "Default")
      (node (ref "X1") (pin "1") (pinfunction "Enable_1") (pintype "power_in+no_connect"))
    )
  )
)
